# pd2.net
KiCad netlist of a schematic drawn in EAGLE
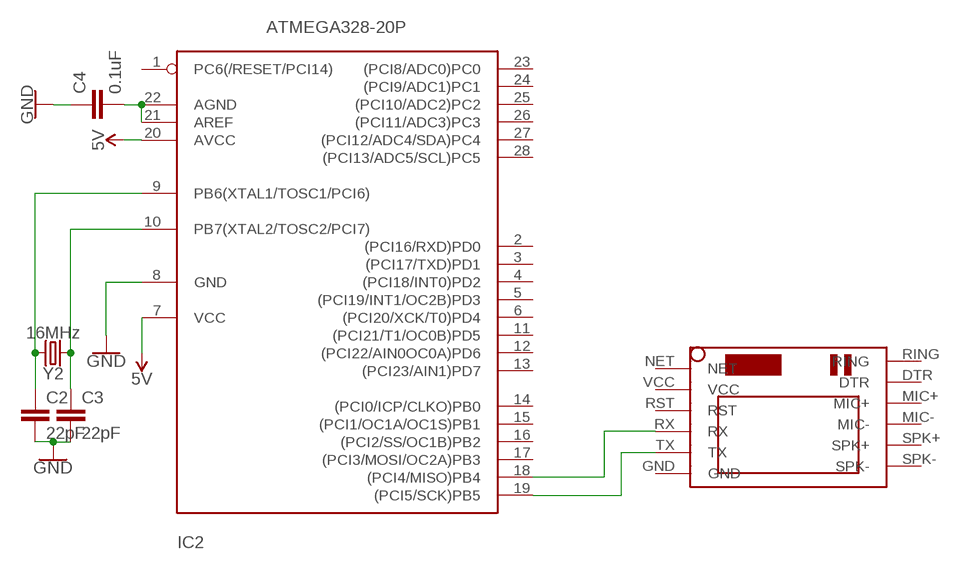
[diagram p0: schematic, sheet 1]

(export (version "E")
  (design (tool "Eeschema 10.0.6"))
  (components
    (comp (ref "C2")
      (value "22pF")
      (footprint "eagle-import:0603")
      (libsource (lib "eagle-import") (part "22PF-0603-50V-5%"))
    )
    (comp (ref "C3")
      (value "22pF")
      (footprint "eagle-import:0603")
      (libsource (lib "eagle-import") (part "22PF-0603-50V-5%"))
    )
    (comp (ref "C4")
      (value "0.1uF")
      (footprint "eagle-import:0402")
      (libsource (lib "eagle-import") (part "0.1UF-0402-16V-10%"))
    )
    (comp (ref "IC2")
      (value "ATMEGA328-20P")
      (footprint "eagle-import:DIL28-3")
      (libsource (lib "eagle-import") (part "ATMEGA328P-20"))
    )
    (comp (ref "U$1")
      (value "SIM800LMODULE")
      (footprint "eagle-import:SIM800LMODULE")
      (libsource (lib "eagle-import") (part "SIM800LMODULE"))
    )
    (comp (ref "Y2")
      (value "16MHz")
      (footprint "eagle-import:HC49US")
      (libsource (lib "eagle-import") (part "CRYSTAL-16MHZPTH-HC49US"))
    )
  )
  (nets
    (net (code "1") (name "5V") (class "Default")
      (node (ref "IC2") (pin "20") (pinfunction "AVCC_20") (pintype "bidirectional"))
      (node (ref "IC2") (pin "7") (pinfunction "VCC_7") (pintype "bidirectional"))
    )
    (net (code "2") (name "GND") (class "Default")
      (node (ref "C2") (pin "2") (pinfunction "2_2") (pintype "passive"))
      (node (ref "C3") (pin "2") (pinfunction "2_2") (pintype "passive"))
      (node (ref "C4") (pin "1") (pinfunction "1_1") (pintype "passive"))
      (node (ref "IC2") (pin "8") (pinfunction "GND_8") (pintype "bidirectional"))
    )
    (net (code "3") (name "Net-(IC2-(PCI4{slash}MISO)PB4)") (class "Default")
      (node (ref "IC2") (pin "18") (pinfunction "(PCI4/MISO)PB4_18") (pintype "bidirectional"))
      (node (ref "U$1") (pin "RX") (pinfunction "RX_RX") (pintype "bidirectional"))
    )
    (net (code "4") (name "Net-(IC2-(PCI5{slash}SCK)PB5)") (class "Default")
      (node (ref "IC2") (pin "19") (pinfunction "(PCI5/SCK)PB5_19") (pintype "bidirectional"))
      (node (ref "U$1") (pin "TX") (pinfunction "TX_TX") (pintype "bidirectional"))
    )
    (net (code "5") (name "Net-(IC2-AGND)") (class "Default")
      (node (ref "C4") (pin "2") (pinfunction "2_2") (pintype "passive"))
      (node (ref "IC2") (pin "21") (pinfunction "AREF_21") (pintype "bidirectional"))
      (node (ref "IC2") (pin "22") (pinfunction "AGND_22") (pintype "bidirectional"))
    )
    (net (code "6") (name "Net-(IC2-PB6(XTAL1{slash}TOSC1{slash}PCI6))") (class "Default")
      (node (ref "C2") (pin "1") (pinfunction "1_1") (pintype "passive"))
      (node (ref "IC2") (pin "9") (pinfunction "PB6(XTAL1/TOSC1/PCI6)_9") (pintype "bidirectional"))
      (node (ref "Y2") (pin "2") (pinfunction "2_2") (pintype "passive"))
    )
    (net (code "7") (name "Net-(IC2-PB7(XTAL2{slash}TOSC2{slash}PCI7))") (class "Default")
      (node (ref "C3") (pin "1") (pinfunction "1_1") (pintype "passive"))
      (node (ref "IC2") (pin "10") (pinfunction "PB7(XTAL2/TOSC2/PCI7)_10") (pintype "bidirectional"))
      (node (ref "Y2") (pin "1") (pinfunction "1_1") (pintype "passive"))
    )
    (net (code "8") (name "unconnected-(IC2-(PCI0{slash}ICP{slash}CLKO)PB0-Pad14)") (class "Default")
      (node (ref "IC2") (pin "14") (pinfunction "(PCI0/ICP/CLKO)PB0_14") (pintype "bidirectional"))
    )
    (net (code "9") (name "unconnected-(IC2-(PCI1{slash}OC1A{slash}OC1S)PB1-Pad15)") (class "Default")
      (node (ref "IC2") (pin "15") (pinfunction "(PCI1/OC1A/OC1S)PB1_15") (pintype "bidirectional"))
    )
    (net (code "10") (name "unconnected-(IC2-(PCI2{slash}SS{slash}OC1B)PB2-Pad16)") (class "Default")
      (node (ref "IC2") (pin "16") (pinfunction "(PCI2/SS/OC1B)PB2_16") (pintype "bidirectional"))
    )
    (net (code "11") (name "unconnected-(IC2-(PCI3{slash}MOSI{slash}OC2A)PB3-Pad17)") (class "Default")
      (node (ref "IC2") (pin "17") (pinfunction "(PCI3/MOSI/OC2A)PB3_17") (pintype "bidirectional"))
    )
    (net (code "12") (name "unconnected-(IC2-(PCI8{slash}ADC0)PC0-Pad23)") (class "Default")
      (node (ref "IC2") (pin "23") (pinfunction "(PCI8/ADC0)PC0_23") (pintype "bidirectional"))
    )
    (net (code "13") (name "unconnected-(IC2-(PCI9{slash}ADC1)PC1-Pad24)") (class "Default")
      (node (ref "IC2") (pin "24") (pinfunction "(PCI9/ADC1)PC1_24") (pintype "bidirectional"))
    )
    (net (code "14") (name "unconnected-(IC2-(PCI10{slash}ADC2)PC2-Pad25)") (class "Default")
      (node (ref "IC2") (pin "25") (pinfunction "(PCI10/ADC2)PC2_25") (pintype "bidirectional"))
    )
    (net (code "15") (name "unconnected-(IC2-(PCI11{slash}ADC3)PC3-Pad26)") (class "Default")
      (node (ref "IC2") (pin "26") (pinfunction "(PCI11/ADC3)PC3_26") (pintype "bidirectional"))
    )
    (net (code "16") (name "unconnected-(IC2-(PCI12{slash}ADC4{slash}SDA)PC4-Pad27)") (class "Default")
      (node (ref "IC2") (pin "27") (pinfunction "(PCI12/ADC4/SDA)PC4_27") (pintype "bidirectional"))
    )
    (net (code "17") (name "unconnected-(IC2-(PCI13{slash}ADC5{slash}SCL)PC5-Pad28)") (class "Default")
      (node (ref "IC2") (pin "28") (pinfunction "(PCI13/ADC5/SCL)PC5_28") (pintype "bidirectional"))
    )
    (net (code "18") (name "unconnected-(IC2-(PCI16{slash}RXD)PD0-Pad2)") (class "Default")
      (node (ref "IC2") (pin "2") (pinfunction "(PCI16/RXD)PD0_2") (pintype "bidirectional"))
    )
    (net (code "19") (name "unconnected-(IC2-(PCI17{slash}TXD)PD1-Pad3)") (class "Default")
      (node (ref "IC2") (pin "3") (pinfunction "(PCI17/TXD)PD1_3") (pintype "bidirectional"))
    )
    (net (code "20") (name "unconnected-(IC2-(PCI18{slash}INT0)PD2-Pad4)") (class "Default")
      (node (ref "IC2") (pin "4") (pinfunction "(PCI18/INT0)PD2_4") (pintype "bidirectional"))
    )
    (net (code "21") (name "unconnected-(IC2-(PCI19{slash}INT1{slash}OC2B)PD3-Pad5)") (class "Default")
      (node (ref "IC2") (pin "5") (pinfunction "(PCI19/INT1/OC2B)PD3_5") (pintype "bidirectional"))
    )
    (net (code "22") (name "unconnected-(IC2-(PCI20{slash}XCK{slash}T0)PD4-Pad6)") (class "Default")
      (node (ref "IC2") (pin "6") (pinfunction "(PCI20/XCK/T0)PD4_6") (pintype "bidirectional"))
    )
    (net (code "23") (name "unconnected-(IC2-(PCI21{slash}T1{slash}OC0B)PD5-Pad11)") (class "Default")
      (node (ref "IC2") (pin "11") (pinfunction "(PCI21/T1/OC0B)PD5_11") (pintype "bidirectional"))
    )
    (net (code "24") (name "unconnected-(IC2-(PCI22{slash}AIN0OC0A)PD6-Pad12)") (class "Default")
      (node (ref "IC2") (pin "12") (pinfunction "(PCI22/AIN0OC0A)PD6_12") (pintype "bidirectional"))
    )
    (net (code "25") (name "unconnected-(IC2-(PCI23{slash}AIN1)PD7-Pad13)") (class "Default")
      (node (ref "IC2") (pin "13") (pinfunction "(PCI23/AIN1)PD7_13") (pintype "bidirectional"))
    )
    (net (code "26") (name "unconnected-(IC2-PC6({slash}RESET{slash}PCI14)-Pad1)") (class "Default")
      (node (ref "IC2") (pin "1") (pinfunction "PC6(/RESET/PCI14)_1") (pintype "bidirectional"))
    )
    (net (code "27") (name "unconnected-(U$1-PadDTR)") (class "Default")
      (node (ref "U$1") (pin "DTR") (pinfunction "DTR_DTR") (pintype "bidirectional"))
    )
    (net (code "28") (name "unconnected-(U$1-PadGND)") (class "Default")
      (node (ref "U$1") (pin "GND") (pinfunction "GND_GND") (pintype "bidirectional"))
    )
    (net (code "29") (name "unconnected-(U$1-PadMIC+)") (class "Default")
      (node (ref "U$1") (pin "MIC+") (pinfunction "MIC+_MIC+") (pintype "bidirectional"))
    )
    (net (code "30") (name "unconnected-(U$1-PadMIC-)") (class "Default")
      (node (ref "U$1") (pin "MIC-") (pinfunction "MIC-_MIC-") (pintype "bidirectional"))
    )
    (net (code "31") (name "unconnected-(U$1-PadNET)") (class "Default")
      (node (ref "U$1") (pin "NET") (pinfunction "NET_NET") (pintype "bidirectional"))
    )
    (net (code "32") (name "unconnected-(U$1-PadRING)") (class "Default")
      (node (ref "U$1") (pin "RING") (pinfunction "RING_RING") (pintype "bidirectional"))
    )
    (net (code "33") (name "unconnected-(U$1-PadRST)") (class "Default")
      (node (ref "U$1") (pin "RST") (pinfunction "RST_RST") (pintype "bidirectional"))
    )
    (net (code "34") (name "unconnected-(U$1-PadSPK+)") (class "Default")
      (node (ref "U$1") (pin "SPK+") (pinfunction "SPK+_SPK+") (pintype "bidirectional"))
    )
    (net (code "35") (name "unconnected-(U$1-PadSPK-)") (class "Default")
      (node (ref "U$1") (pin "SPK-") (pinfunction "SPK-_SPK-") (pintype "bidirectional"))
    )
    (net (code "36") (name "unconnected-(U$1-PadVCC)") (class "Default")
      (node (ref "U$1") (pin "VCC") (pinfunction "VCC_VCC") (pintype "bidirectional"))
    )
  )
)
